# 00.net
KiCad netlist of a schematic drawn in EasyEDA
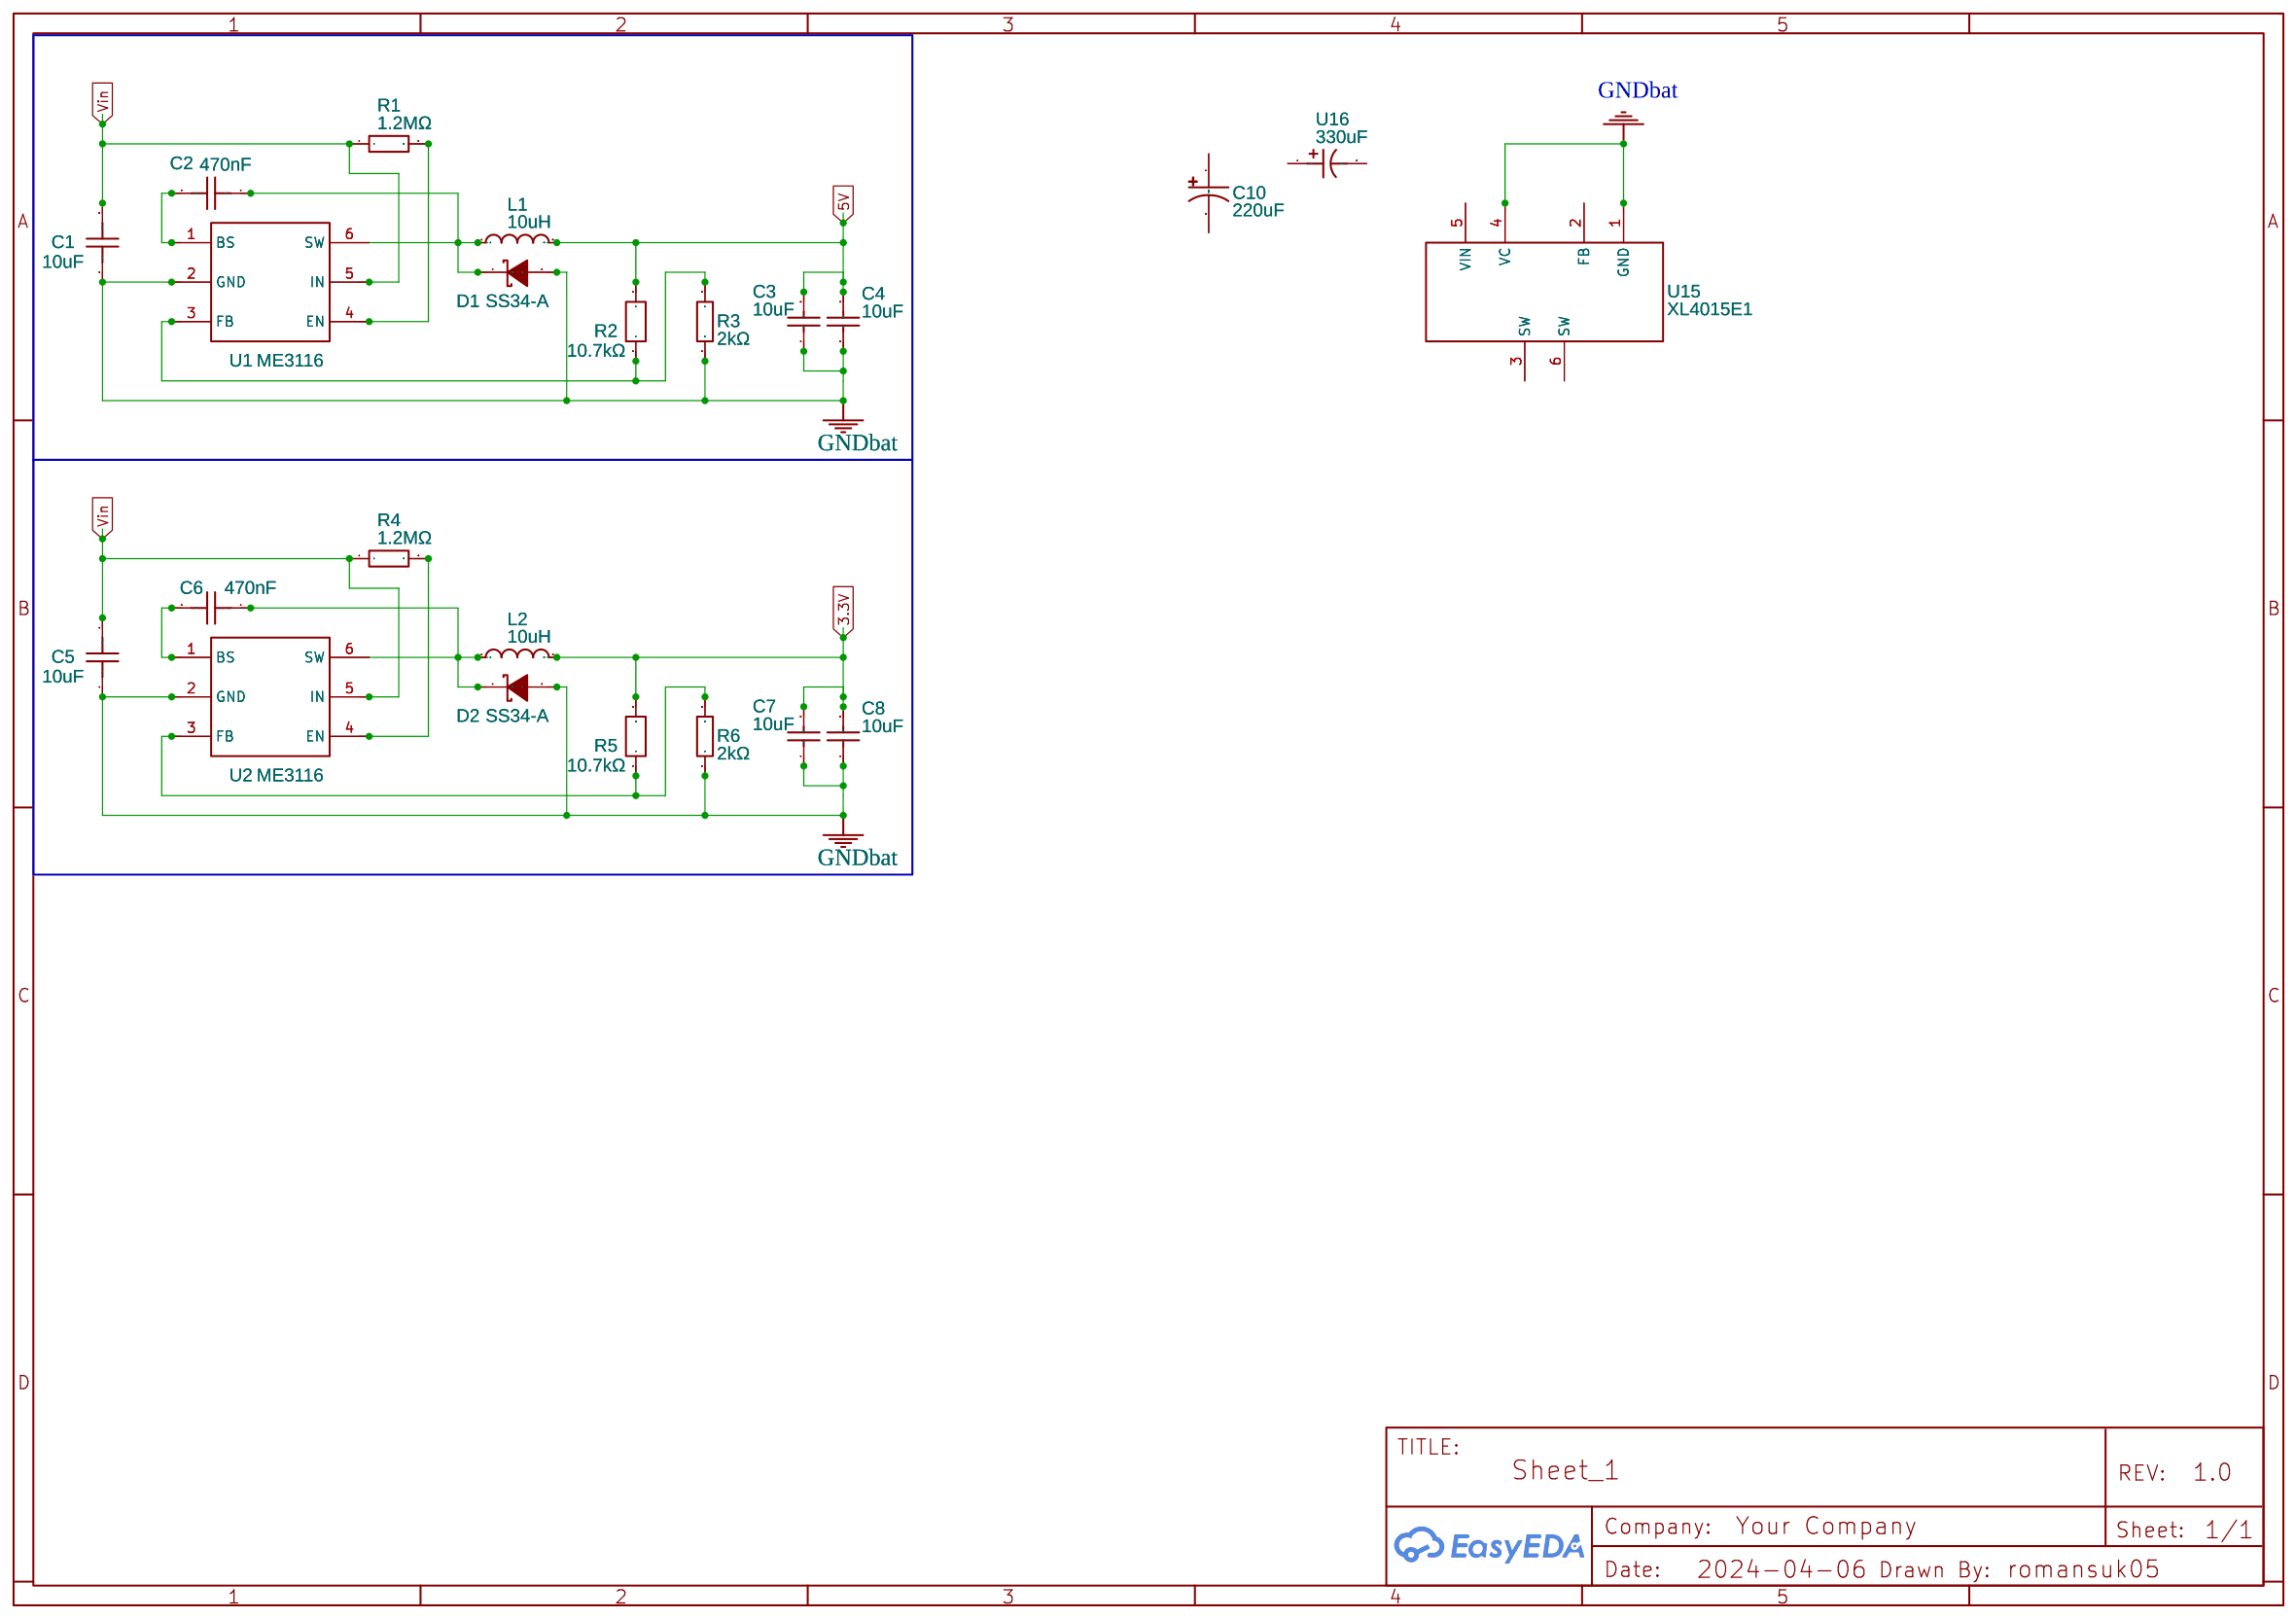
[diagram p0: schematic sheet]

(export (version "E")
  (design (tool "Eeschema 10.0.6"))
  (components
    (comp (ref "C1")
      (value "10uF")
      (fields
        (field (name "Manufacturer Part") "TCC1206X7R106K250HT")
        (field (name "Manufacturer") "CCTC(三环)")
      )
      (libsource (lib "") (part "TCC1206X7R106K250HT"))
    )
    (comp (ref "C2")
      (value "470nF")
      (fields
        (field (name "Manufacturer Part") "TCC1206X7R474K500FT")
        (field (name "Manufacturer") "CCTC(三环)")
      )
      (libsource (lib "") (part "TCC1206X7R474K500FT"))
    )
    (comp (ref "C3")
      (value "10uF")
      (fields
        (field (name "Manufacturer Part") "TMK316B7106KL-TD")
        (field (name "Manufacturer") "TAIYO YUDEN(太诱)")
      )
      (libsource (lib "") (part "TMK316B7106KL-TD"))
    )
    (comp (ref "C4")
      (value "10uF")
      (fields
        (field (name "Manufacturer Part") "TMK316B7106KL-TD")
        (field (name "Manufacturer") "TAIYO YUDEN(太诱)")
      )
      (libsource (lib "") (part "TMK316B7106KL-TD"))
    )
    (comp (ref "C5")
      (value "10uF")
      (fields
        (field (name "Manufacturer Part") "TCC1206X7R106K250HT")
        (field (name "Manufacturer") "CCTC(三环)")
      )
      (libsource (lib "") (part "TCC1206X7R106K250HT"))
    )
    (comp (ref "C6")
      (value "470nF")
      (fields
        (field (name "Manufacturer Part") "TCC1206X7R474K500FT")
        (field (name "Manufacturer") "CCTC(三环)")
      )
      (libsource (lib "") (part "TCC1206X7R474K500FT"))
    )
    (comp (ref "C7")
      (value "10uF")
      (fields
        (field (name "Manufacturer Part") "TMK316B7106KL-TD")
        (field (name "Manufacturer") "TAIYO YUDEN(太诱)")
      )
      (libsource (lib "") (part "TMK316B7106KL-TD"))
    )
    (comp (ref "C8")
      (value "10uF")
      (fields
        (field (name "Manufacturer Part") "TMK316B7106KL-TD")
        (field (name "Manufacturer") "TAIYO YUDEN(太诱)")
      )
      (libsource (lib "") (part "TMK316B7106KL-TD"))
    )
    (comp (ref "C10")
      (value "220uF")
      (fields
        (field (name "Manufacturer Part") "BXJ50V220M10*10 10TP")
        (field (name "Manufacturer") "SAMYOUNG(韩国三莹)")
      )
      (libsource (lib "") (part "BXJ-50V220-10*10"))
    )
    (comp (ref "D1")
      (value "SS34-A")
      (fields (field (name "Manufacturer") "FMS(美丽微)"))
      (libsource (lib "") (part "SS34-A"))
    )
    (comp (ref "D2")
      (value "SS34-A")
      (fields (field (name "Manufacturer") "FMS(美丽微)"))
      (libsource (lib "") (part "SS34-A"))
    )
    (comp (ref "L1")
      (value "10uH")
      (fields (field (name "Manufacturer Part") "CY75SX-10UH") (field (name "Manufacturer") "SHOU HAN(首韩)"))
      (libsource (lib "") (part "CY75SX-10UH"))
    )
    (comp (ref "L2")
      (value "10uH")
      (fields (field (name "Manufacturer Part") "CY75SX-10UH") (field (name "Manufacturer") "SHOU HAN(首韩)"))
      (libsource (lib "") (part "CY75SX-10UH"))
    )
    (comp (ref "R1")
      (value "1.2MΩ")
      (fields (field (name "Manufacturer Part") "WR12W1204FTL") (field (name "Manufacturer") "Walsin(华新科)"))
      (libsource (lib "") (part "WR12W1204FTL"))
    )
    (comp (ref "R2")
      (value "10.7kΩ")
      (fields (field (name "Manufacturer Part") "RC1206FR-0710K7L") (field (name "Manufacturer") "YAGEO(国巨)"))
      (libsource (lib "") (part "RC1206FR-0710K7L"))
    )
    (comp (ref "R3")
      (value "2kΩ")
      (fields (field (name "Manufacturer Part") "RTT06202JTP") (field (name "Manufacturer") "RALEC(旺诠)"))
      (libsource (lib "") (part "RTT06202JTP"))
    )
    (comp (ref "R4")
      (value "1.2MΩ")
      (fields (field (name "Manufacturer Part") "WR12W1204FTL") (field (name "Manufacturer") "Walsin(华新科)"))
      (libsource (lib "") (part "WR12W1204FTL"))
    )
    (comp (ref "R5")
      (value "10.7kΩ")
      (fields (field (name "Manufacturer Part") "RC1206FR-0710K7L") (field (name "Manufacturer") "YAGEO(国巨)"))
      (libsource (lib "") (part "RC1206FR-0710K7L"))
    )
    (comp (ref "R6")
      (value "2kΩ")
      (fields (field (name "Manufacturer Part") "RTT06202JTP") (field (name "Manufacturer") "RALEC(旺诠)"))
      (libsource (lib "") (part "RTT06202JTP"))
    )
    (comp (ref "U1")
      (value "ME3116")
      (fields (field (name "Manufacturer Part") "ME3116AM6G") (field (name "Manufacturer") "MICRONE(南京微盟)"))
      (libsource (lib "") (part "ME3116"))
    )
    (comp (ref "U2")
      (value "ME3116")
      (fields (field (name "Manufacturer Part") "ME3116AM6G") (field (name "Manufacturer") "MICRONE(南京微盟)"))
      (libsource (lib "") (part "ME3116"))
    )
    (comp (ref "U15")
      (value "XL4015E1")
      (fields (field (name "Manufacturer") "XLSEMI(芯龙)"))
      (libsource (lib "") (part "XL4015E1"))
    )
    (comp (ref "U16")
      (value "330uF")
      (fields (field (name "Manufacturer Part") "189RV0016") (field (name "Manufacturer") "KNSCHA(科尼盛)"))
      (libsource (lib "") (part "189RV0016"))
    )
  )
  (nets
    (net (code "1") (name "3.3V") (class "Default")
      (node (ref "C7") (pin "2") (pinfunction "2_2") (pintype "input"))
      (node (ref "C8") (pin "2") (pinfunction "2_2") (pintype "input"))
      (node (ref "L2") (pin "2") (pinfunction "2_2") (pintype "unspecified"))
      (node (ref "R5") (pin "2") (pinfunction "2_2") (pintype "unspecified"))
    )
    (net (code "2") (name "5V") (class "Default")
      (node (ref "C3") (pin "2") (pinfunction "2_2") (pintype "input"))
      (node (ref "C4") (pin "2") (pinfunction "2_2") (pintype "input"))
      (node (ref "L1") (pin "2") (pinfunction "2_2") (pintype "unspecified"))
      (node (ref "R2") (pin "2") (pinfunction "2_2") (pintype "unspecified"))
    )
    (net (code "3") (name "GNDbat") (class "Default")
      (node (ref "C1") (pin "1") (pinfunction "1_1") (pintype "unspecified"))
      (node (ref "C3") (pin "1") (pinfunction "1_1") (pintype "input"))
      (node (ref "C4") (pin "1") (pinfunction "1_1") (pintype "input"))
      (node (ref "C5") (pin "1") (pinfunction "1_1") (pintype "unspecified"))
      (node (ref "C7") (pin "1") (pinfunction "1_1") (pintype "input"))
      (node (ref "C8") (pin "1") (pinfunction "1_1") (pintype "input"))
      (node (ref "D1") (pin "2") (pinfunction "A_2") (pintype "unspecified"))
      (node (ref "D2") (pin "2") (pinfunction "A_2") (pintype "unspecified"))
      (node (ref "R3") (pin "1") (pinfunction "1_1") (pintype "input"))
      (node (ref "R6") (pin "1") (pinfunction "1_1") (pintype "input"))
      (node (ref "U1") (pin "2") (pinfunction "GND_2") (pintype "unspecified"))
      (node (ref "U15") (pin "1") (pinfunction "GND_1") (pintype "unspecified"))
      (node (ref "U15") (pin "4") (pinfunction "VC_4") (pintype "unspecified"))
      (node (ref "U2") (pin "2") (pinfunction "GND_2") (pintype "unspecified"))
    )
    (net (code "4") (name "Net-(D1-C)") (class "Default")
      (node (ref "C2") (pin "1") (pinfunction "1_1") (pintype "unspecified"))
      (node (ref "D1") (pin "1") (pinfunction "C_1") (pintype "unspecified"))
      (node (ref "L1") (pin "1") (pinfunction "1_1") (pintype "unspecified"))
      (node (ref "U1") (pin "6") (pinfunction "SW_6") (pintype "unspecified"))
    )
    (net (code "5") (name "Net-(D2-C)") (class "Default")
      (node (ref "C6") (pin "1") (pinfunction "1_1") (pintype "unspecified"))
      (node (ref "D2") (pin "1") (pinfunction "C_1") (pintype "unspecified"))
      (node (ref "L2") (pin "1") (pinfunction "1_1") (pintype "unspecified"))
      (node (ref "U2") (pin "6") (pinfunction "SW_6") (pintype "unspecified"))
    )
    (net (code "6") (name "Net-(U1-BS)") (class "Default")
      (node (ref "C2") (pin "2") (pinfunction "2_2") (pintype "unspecified"))
      (node (ref "U1") (pin "1") (pinfunction "BS_1") (pintype "unspecified"))
    )
    (net (code "7") (name "Net-(U1-EN)") (class "Default")
      (node (ref "R1") (pin "2") (pinfunction "2_2") (pintype "unspecified"))
      (node (ref "U1") (pin "4") (pinfunction "EN_4") (pintype "unspecified"))
    )
    (net (code "8") (name "Net-(U1-FB)") (class "Default")
      (node (ref "R2") (pin "1") (pinfunction "1_1") (pintype "unspecified"))
      (node (ref "R3") (pin "2") (pinfunction "2_2") (pintype "input"))
      (node (ref "U1") (pin "3") (pinfunction "FB_3") (pintype "unspecified"))
    )
    (net (code "9") (name "Net-(U2-BS)") (class "Default")
      (node (ref "C6") (pin "2") (pinfunction "2_2") (pintype "unspecified"))
      (node (ref "U2") (pin "1") (pinfunction "BS_1") (pintype "unspecified"))
    )
    (net (code "10") (name "Net-(U2-EN)") (class "Default")
      (node (ref "R4") (pin "2") (pinfunction "2_2") (pintype "unspecified"))
      (node (ref "U2") (pin "4") (pinfunction "EN_4") (pintype "unspecified"))
    )
    (net (code "11") (name "Net-(U2-FB)") (class "Default")
      (node (ref "R5") (pin "1") (pinfunction "1_1") (pintype "unspecified"))
      (node (ref "R6") (pin "2") (pinfunction "2_2") (pintype "input"))
      (node (ref "U2") (pin "3") (pinfunction "FB_3") (pintype "unspecified"))
    )
    (net (code "12") (name "Vin") (class "Default")
      (node (ref "C1") (pin "2") (pinfunction "2_2") (pintype "unspecified"))
      (node (ref "C5") (pin "2") (pinfunction "2_2") (pintype "unspecified"))
      (node (ref "R1") (pin "1") (pinfunction "1_1") (pintype "unspecified"))
      (node (ref "R4") (pin "1") (pinfunction "1_1") (pintype "unspecified"))
      (node (ref "U1") (pin "5") (pinfunction "IN_5") (pintype "unspecified"))
      (node (ref "U2") (pin "5") (pinfunction "IN_5") (pintype "unspecified"))
    )
    (net (code "13") (name "unconnected-(C10-Pad1)") (class "Default")
      (node (ref "C10") (pin "1") (pinfunction "1_1") (pintype "unspecified"))
    )
    (net (code "14") (name "unconnected-(C10-Pad2)") (class "Default")
      (node (ref "C10") (pin "2") (pinfunction "2_2") (pintype "unspecified"))
    )
    (net (code "15") (name "unconnected-(U15-FB-Pad2)") (class "Default")
      (node (ref "U15") (pin "2") (pinfunction "FB_2") (pintype "unspecified"))
    )
    (net (code "16") (name "unconnected-(U15-SW-Pad3)") (class "Default")
      (node (ref "U15") (pin "3") (pinfunction "SW_3") (pintype "unspecified"))
    )
    (net (code "17") (name "unconnected-(U15-SW-Pad6)") (class "Default")
      (node (ref "U15") (pin "6") (pinfunction "SW_6") (pintype "unspecified"))
    )
    (net (code "18") (name "unconnected-(U15-VIN-Pad5)") (class "Default")
      (node (ref "U15") (pin "5") (pinfunction "VIN_5") (pintype "unspecified"))
    )
    (net (code "19") (name "unconnected-(U16-Pad1)") (class "Default")
      (node (ref "U16") (pin "1") (pinfunction "1_1") (pintype "input"))
    )
    (net (code "20") (name "unconnected-(U16-Pad2)") (class "Default")
      (node (ref "U16") (pin "2") (pinfunction "2_2") (pintype "input"))
    )
  )
)
